# Laser_Array_Temp_Low_BRD_V2_2.net
KiCad netlist of a schematic drawn in EAGLE
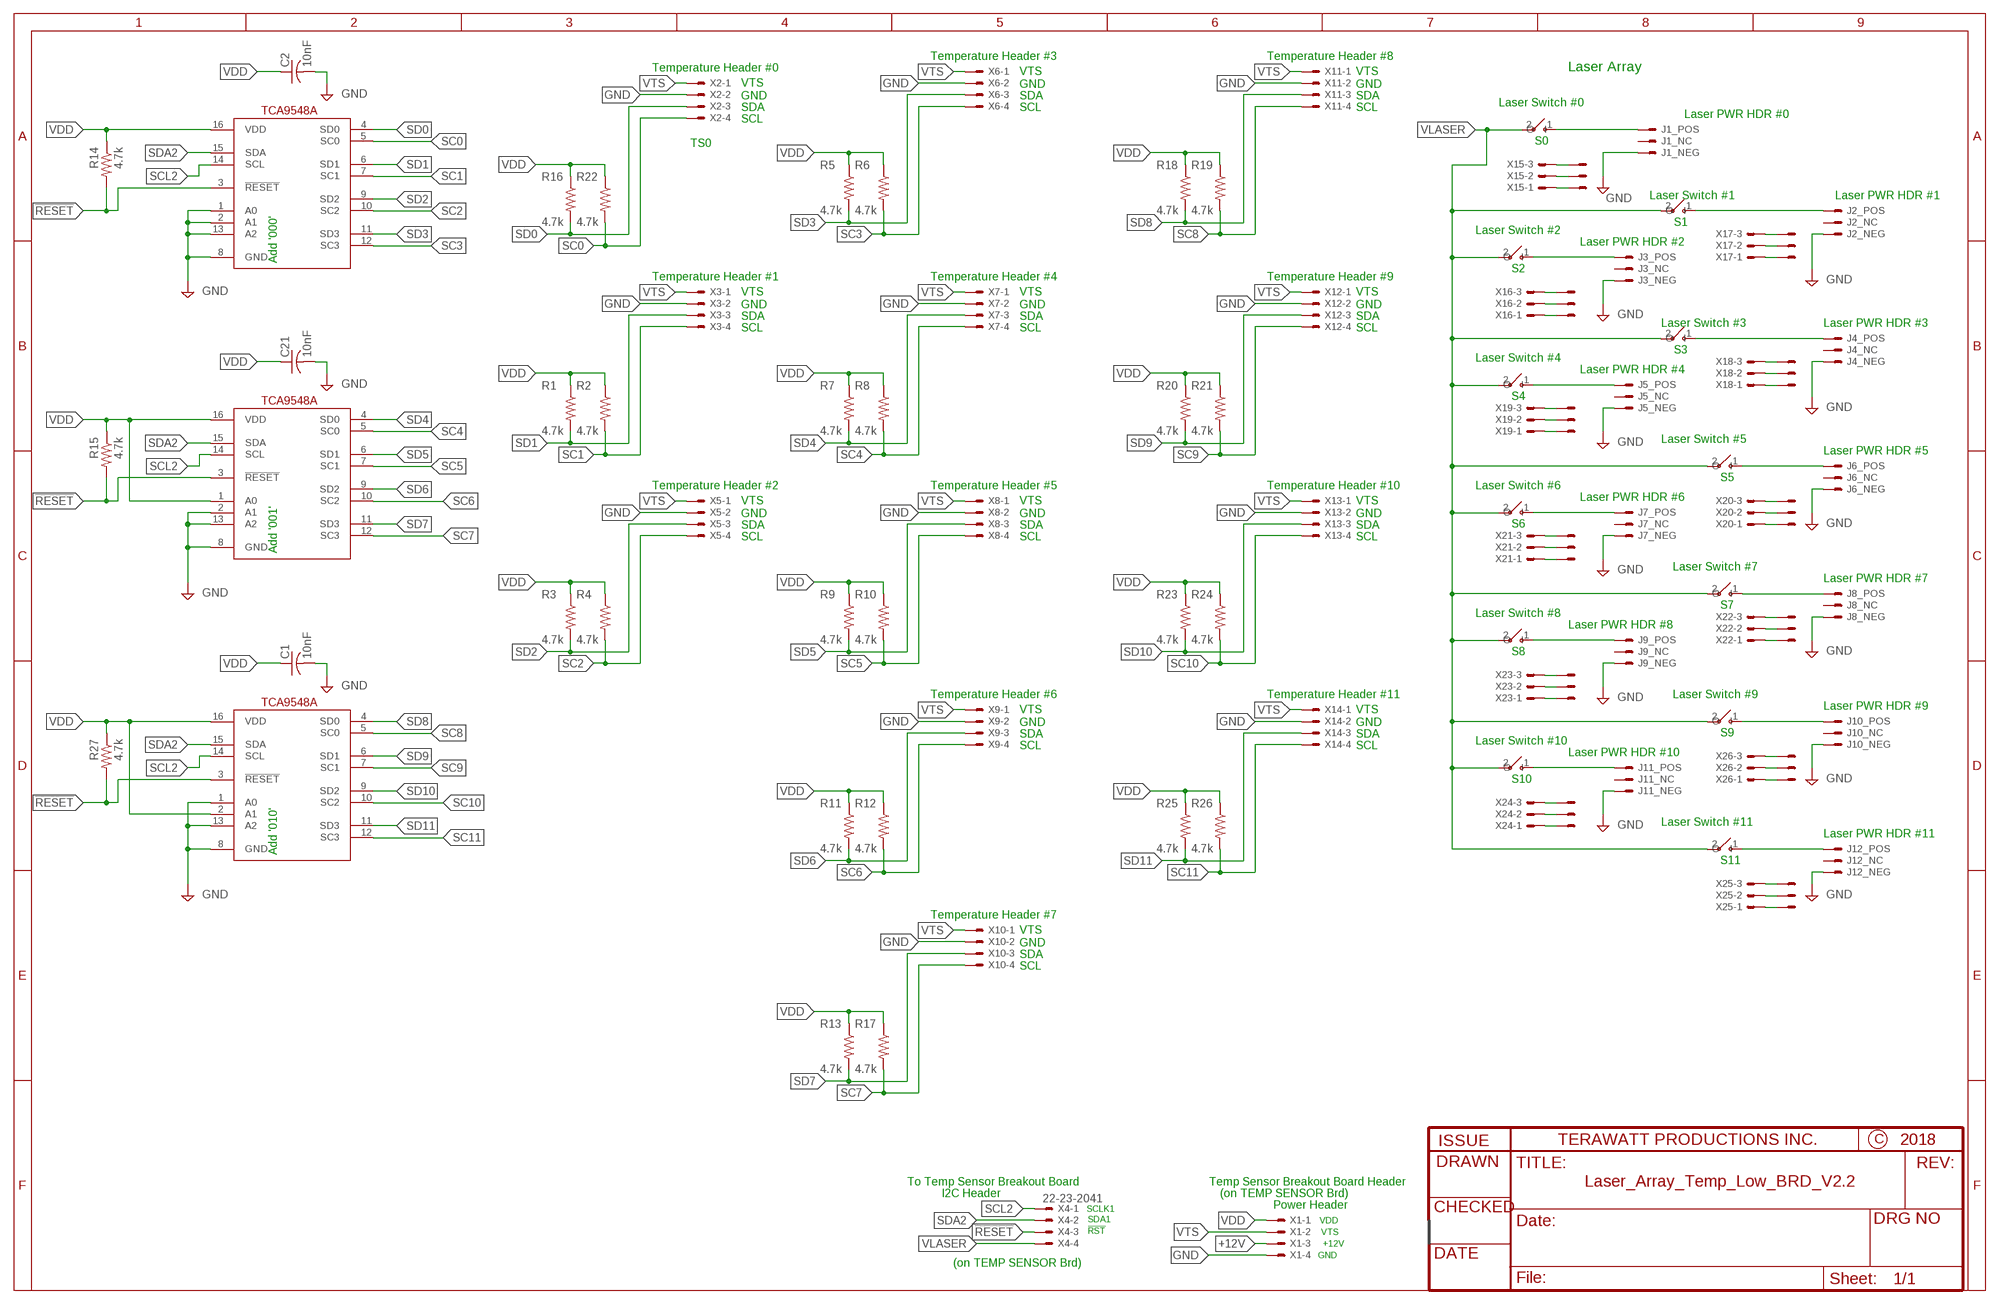
[diagram p0: schematic, sheet 1]

(export (version "E")
  (design (tool "Eeschema 10.0.6"))
  (components
    (comp (ref "C1")
      (value "10nF")
      (footprint "eagle-import:C0805")
      (libsource (lib "eagle-import") (part "C-USC0805"))
    )
    (comp (ref "C2")
      (value "10nF")
      (footprint "eagle-import:C0805")
      (libsource (lib "eagle-import") (part "C-USC0805"))
    )
    (comp (ref "C21")
      (value "10nF")
      (footprint "eagle-import:C0805")
      (libsource (lib "eagle-import") (part "C-USC0805"))
    )
    (comp (ref "J1")
      (value "LASER_MOD")
      (footprint "eagle-import:LASER_MOD")
      (libsource (lib "eagle-import") (part "LASER_MOD"))
    )
    (comp (ref "J2")
      (value "LASER_MOD")
      (footprint "eagle-import:LASER_MOD")
      (libsource (lib "eagle-import") (part "LASER_MOD"))
    )
    (comp (ref "J3")
      (value "LASER_MOD")
      (footprint "eagle-import:LASER_MOD")
      (libsource (lib "eagle-import") (part "LASER_MOD"))
    )
    (comp (ref "J4")
      (value "LASER_MOD")
      (footprint "eagle-import:LASER_MOD")
      (libsource (lib "eagle-import") (part "LASER_MOD"))
    )
    (comp (ref "J5")
      (value "LASER_MOD")
      (footprint "eagle-import:LASER_MOD")
      (libsource (lib "eagle-import") (part "LASER_MOD"))
    )
    (comp (ref "J6")
      (value "LASER_MOD")
      (footprint "eagle-import:LASER_MOD")
      (libsource (lib "eagle-import") (part "LASER_MOD"))
    )
    (comp (ref "J7")
      (value "LASER_MOD")
      (footprint "eagle-import:LASER_MOD")
      (libsource (lib "eagle-import") (part "LASER_MOD"))
    )
    (comp (ref "J8")
      (value "LASER_MOD")
      (footprint "eagle-import:LASER_MOD")
      (libsource (lib "eagle-import") (part "LASER_MOD"))
    )
    (comp (ref "J9")
      (value "LASER_MOD")
      (footprint "eagle-import:LASER_MOD")
      (libsource (lib "eagle-import") (part "LASER_MOD"))
    )
    (comp (ref "J10")
      (value "LASER_MOD")
      (footprint "eagle-import:LASER_MOD")
      (libsource (lib "eagle-import") (part "LASER_MOD"))
    )
    (comp (ref "J11")
      (value "LASER_MOD")
      (footprint "eagle-import:LASER_MOD")
      (libsource (lib "eagle-import") (part "LASER_MOD"))
    )
    (comp (ref "J12")
      (value "LASER_MOD")
      (footprint "eagle-import:LASER_MOD")
      (libsource (lib "eagle-import") (part "LASER_MOD"))
    )
    (comp (ref "R1")
      (value "4.7k")
      (footprint "eagle-import:M0805")
      (libsource (lib "eagle-import") (part "R-US_M0805"))
    )
    (comp (ref "R2")
      (value "4.7k")
      (footprint "eagle-import:M0805")
      (libsource (lib "eagle-import") (part "R-US_M0805"))
    )
    (comp (ref "R3")
      (value "4.7k")
      (footprint "eagle-import:M0805")
      (libsource (lib "eagle-import") (part "R-US_M0805"))
    )
    (comp (ref "R4")
      (value "4.7k")
      (footprint "eagle-import:M0805")
      (libsource (lib "eagle-import") (part "R-US_M0805"))
    )
    (comp (ref "R5")
      (value "4.7k")
      (footprint "eagle-import:M0805")
      (libsource (lib "eagle-import") (part "R-US_M0805"))
    )
    (comp (ref "R6")
      (value "4.7k")
      (footprint "eagle-import:M0805")
      (libsource (lib "eagle-import") (part "R-US_M0805"))
    )
    (comp (ref "R7")
      (value "4.7k")
      (footprint "eagle-import:M0805")
      (libsource (lib "eagle-import") (part "R-US_M0805"))
    )
    (comp (ref "R8")
      (value "4.7k")
      (footprint "eagle-import:M0805")
      (libsource (lib "eagle-import") (part "R-US_M0805"))
    )
    (comp (ref "R9")
      (value "4.7k")
      (footprint "eagle-import:M0805")
      (libsource (lib "eagle-import") (part "R-US_M0805"))
    )
    (comp (ref "R10")
      (value "4.7k")
      (footprint "eagle-import:M0805")
      (libsource (lib "eagle-import") (part "R-US_M0805"))
    )
    (comp (ref "R11")
      (value "4.7k")
      (footprint "eagle-import:M0805")
      (libsource (lib "eagle-import") (part "R-US_M0805"))
    )
    (comp (ref "R12")
      (value "4.7k")
      (footprint "eagle-import:M0805")
      (libsource (lib "eagle-import") (part "R-US_M0805"))
    )
    (comp (ref "R13")
      (value "4.7k")
      (footprint "eagle-import:M0805")
      (libsource (lib "eagle-import") (part "R-US_M0805"))
    )
    (comp (ref "R14")
      (value "4.7k")
      (footprint "eagle-import:M0805")
      (libsource (lib "eagle-import") (part "R-US_M0805"))
    )
    (comp (ref "R15")
      (value "4.7k")
      (footprint "eagle-import:M0805")
      (libsource (lib "eagle-import") (part "R-US_M0805"))
    )
    (comp (ref "R16")
      (value "4.7k")
      (footprint "eagle-import:M0805")
      (libsource (lib "eagle-import") (part "R-US_M0805"))
    )
    (comp (ref "R17")
      (value "4.7k")
      (footprint "eagle-import:M0805")
      (libsource (lib "eagle-import") (part "R-US_M0805"))
    )
    (comp (ref "R18")
      (value "4.7k")
      (footprint "eagle-import:M0805")
      (libsource (lib "eagle-import") (part "R-US_M0805"))
    )
    (comp (ref "R19")
      (value "4.7k")
      (footprint "eagle-import:M0805")
      (libsource (lib "eagle-import") (part "R-US_M0805"))
    )
    (comp (ref "R20")
      (value "4.7k")
      (footprint "eagle-import:M0805")
      (libsource (lib "eagle-import") (part "R-US_M0805"))
    )
    (comp (ref "R21")
      (value "4.7k")
      (footprint "eagle-import:M0805")
      (libsource (lib "eagle-import") (part "R-US_M0805"))
    )
    (comp (ref "R22")
      (value "4.7k")
      (footprint "eagle-import:M0805")
      (libsource (lib "eagle-import") (part "R-US_M0805"))
    )
    (comp (ref "R23")
      (value "4.7k")
      (footprint "eagle-import:M0805")
      (libsource (lib "eagle-import") (part "R-US_M0805"))
    )
    (comp (ref "R24")
      (value "4.7k")
      (footprint "eagle-import:M0805")
      (libsource (lib "eagle-import") (part "R-US_M0805"))
    )
    (comp (ref "R25")
      (value "4.7k")
      (footprint "eagle-import:M0805")
      (libsource (lib "eagle-import") (part "R-US_M0805"))
    )
    (comp (ref "R26")
      (value "4.7k")
      (footprint "eagle-import:M0805")
      (libsource (lib "eagle-import") (part "R-US_M0805"))
    )
    (comp (ref "R27")
      (value "4.7k")
      (footprint "eagle-import:M0805")
      (libsource (lib "eagle-import") (part "R-US_M0805"))
    )
    (comp (ref "S13")
      (value "TOGGLE_SPST")
      (footprint "eagle-import:22-23-2021")
      (libsource (lib "eagle-import") (part "TOGGLE_SPST"))
    )
    (comp (ref "S14")
      (value "TOGGLE_SPST")
      (footprint "eagle-import:22-23-2021")
      (libsource (lib "eagle-import") (part "TOGGLE_SPST"))
    )
    (comp (ref "S15")
      (value "TOGGLE_SPST")
      (footprint "eagle-import:22-23-2021")
      (libsource (lib "eagle-import") (part "TOGGLE_SPST"))
    )
    (comp (ref "S16")
      (value "TOGGLE_SPST")
      (footprint "eagle-import:22-23-2021")
      (libsource (lib "eagle-import") (part "TOGGLE_SPST"))
    )
    (comp (ref "S17")
      (value "TOGGLE_SPST")
      (footprint "eagle-import:22-23-2021")
      (libsource (lib "eagle-import") (part "TOGGLE_SPST"))
    )
    (comp (ref "S18")
      (value "TOGGLE_SPST")
      (footprint "eagle-import:22-23-2021")
      (libsource (lib "eagle-import") (part "TOGGLE_SPST"))
    )
    (comp (ref "S19")
      (value "TOGGLE_SPST")
      (footprint "eagle-import:22-23-2021")
      (libsource (lib "eagle-import") (part "TOGGLE_SPST"))
    )
    (comp (ref "S20")
      (value "TOGGLE_SPST")
      (footprint "eagle-import:22-23-2021")
      (libsource (lib "eagle-import") (part "TOGGLE_SPST"))
    )
    (comp (ref "S21")
      (value "TOGGLE_SPST")
      (footprint "eagle-import:22-23-2021")
      (libsource (lib "eagle-import") (part "TOGGLE_SPST"))
    )
    (comp (ref "S22")
      (value "TOGGLE_SPST")
      (footprint "eagle-import:22-23-2021")
      (libsource (lib "eagle-import") (part "TOGGLE_SPST"))
    )
    (comp (ref "S23")
      (value "TOGGLE_SPST")
      (footprint "eagle-import:22-23-2021")
      (libsource (lib "eagle-import") (part "TOGGLE_SPST"))
    )
    (comp (ref "S24")
      (value "TOGGLE_SPST")
      (footprint "eagle-import:22-23-2021")
      (libsource (lib "eagle-import") (part "TOGGLE_SPST"))
    )
    (comp (ref "U$1")
      (value "SINGLE_PAD")
      (footprint "eagle-import:SINGLE_PAD")
      (libsource (lib "eagle-import") (part "SINGLE_PAD"))
    )
    (comp (ref "U$2")
      (value "SINGLE_PAD")
      (footprint "eagle-import:SINGLE_PAD")
      (libsource (lib "eagle-import") (part "SINGLE_PAD"))
    )
    (comp (ref "U$3")
      (value "SINGLE_PAD")
      (footprint "eagle-import:SINGLE_PAD")
      (libsource (lib "eagle-import") (part "SINGLE_PAD"))
    )
    (comp (ref "U$4")
      (value "SINGLE_PAD")
      (footprint "eagle-import:SINGLE_PAD")
      (libsource (lib "eagle-import") (part "SINGLE_PAD"))
    )
    (comp (ref "U$5")
      (value "SINGLE_PAD")
      (footprint "eagle-import:SINGLE_PAD")
      (libsource (lib "eagle-import") (part "SINGLE_PAD"))
    )
    (comp (ref "U$6")
      (value "SINGLE_PAD")
      (footprint "eagle-import:SINGLE_PAD")
      (libsource (lib "eagle-import") (part "SINGLE_PAD"))
    )
    (comp (ref "U$7")
      (value "SINGLE_PAD")
      (footprint "eagle-import:SINGLE_PAD")
      (libsource (lib "eagle-import") (part "SINGLE_PAD"))
    )
    (comp (ref "U$8")
      (value "SINGLE_PAD")
      (footprint "eagle-import:SINGLE_PAD")
      (libsource (lib "eagle-import") (part "SINGLE_PAD"))
    )
    (comp (ref "U$9")
      (value "SINGLE_PAD")
      (footprint "eagle-import:SINGLE_PAD")
      (libsource (lib "eagle-import") (part "SINGLE_PAD"))
    )
    (comp (ref "U$10")
      (value "SINGLE_PAD")
      (footprint "eagle-import:SINGLE_PAD")
      (libsource (lib "eagle-import") (part "SINGLE_PAD"))
    )
    (comp (ref "U$11")
      (value "SINGLE_PAD")
      (footprint "eagle-import:SINGLE_PAD")
      (libsource (lib "eagle-import") (part "SINGLE_PAD"))
    )
    (comp (ref "U$12")
      (value "SINGLE_PAD")
      (footprint "eagle-import:SINGLE_PAD")
      (libsource (lib "eagle-import") (part "SINGLE_PAD"))
    )
    (comp (ref "U$13")
      (value "SINGLE_PAD")
      (footprint "eagle-import:SINGLE_PAD")
      (libsource (lib "eagle-import") (part "SINGLE_PAD"))
    )
    (comp (ref "U$14")
      (value "SINGLE_PAD")
      (footprint "eagle-import:SINGLE_PAD")
      (libsource (lib "eagle-import") (part "SINGLE_PAD"))
    )
    (comp (ref "U$15")
      (value "SINGLE_PAD")
      (footprint "eagle-import:SINGLE_PAD")
      (libsource (lib "eagle-import") (part "SINGLE_PAD"))
    )
    (comp (ref "U$16")
      (value "SINGLE_PAD")
      (footprint "eagle-import:SINGLE_PAD")
      (libsource (lib "eagle-import") (part "SINGLE_PAD"))
    )
    (comp (ref "U$17")
      (value "SINGLE_PAD")
      (footprint "eagle-import:SINGLE_PAD")
      (libsource (lib "eagle-import") (part "SINGLE_PAD"))
    )
    (comp (ref "U$18")
      (value "SINGLE_PAD")
      (footprint "eagle-import:SINGLE_PAD")
      (libsource (lib "eagle-import") (part "SINGLE_PAD"))
    )
    (comp (ref "U$19")
      (value "SINGLE_PAD")
      (footprint "eagle-import:SINGLE_PAD")
      (libsource (lib "eagle-import") (part "SINGLE_PAD"))
    )
    (comp (ref "U$20")
      (value "SINGLE_PAD")
      (footprint "eagle-import:SINGLE_PAD")
      (libsource (lib "eagle-import") (part "SINGLE_PAD"))
    )
    (comp (ref "U$21")
      (value "SINGLE_PAD")
      (footprint "eagle-import:SINGLE_PAD")
      (libsource (lib "eagle-import") (part "SINGLE_PAD"))
    )
    (comp (ref "U$22")
      (value "SINGLE_PAD")
      (footprint "eagle-import:SINGLE_PAD")
      (libsource (lib "eagle-import") (part "SINGLE_PAD"))
    )
    (comp (ref "U$23")
      (value "SINGLE_PAD")
      (footprint "eagle-import:SINGLE_PAD")
      (libsource (lib "eagle-import") (part "SINGLE_PAD"))
    )
    (comp (ref "U$24")
      (value "SINGLE_PAD")
      (footprint "eagle-import:SINGLE_PAD")
      (libsource (lib "eagle-import") (part "SINGLE_PAD"))
    )
    (comp (ref "U$25")
      (value "SINGLE_PAD")
      (footprint "eagle-import:SINGLE_PAD")
      (libsource (lib "eagle-import") (part "SINGLE_PAD"))
    )
    (comp (ref "U$26")
      (value "SINGLE_PAD")
      (footprint "eagle-import:SINGLE_PAD")
      (libsource (lib "eagle-import") (part "SINGLE_PAD"))
    )
    (comp (ref "U$27")
      (value "SINGLE_PAD")
      (footprint "eagle-import:SINGLE_PAD")
      (libsource (lib "eagle-import") (part "SINGLE_PAD"))
    )
    (comp (ref "U$28")
      (value "SINGLE_PAD")
      (footprint "eagle-import:SINGLE_PAD")
      (libsource (lib "eagle-import") (part "SINGLE_PAD"))
    )
    (comp (ref "U$29")
      (value "SINGLE_PAD")
      (footprint "eagle-import:SINGLE_PAD")
      (libsource (lib "eagle-import") (part "SINGLE_PAD"))
    )
    (comp (ref "U$30")
      (value "SINGLE_PAD")
      (footprint "eagle-import:SINGLE_PAD")
      (libsource (lib "eagle-import") (part "SINGLE_PAD"))
    )
    (comp (ref "U$31")
      (value "SINGLE_PAD")
      (footprint "eagle-import:SINGLE_PAD")
      (libsource (lib "eagle-import") (part "SINGLE_PAD"))
    )
    (comp (ref "U$32")
      (value "SINGLE_PAD")
      (footprint "eagle-import:SINGLE_PAD")
      (libsource (lib "eagle-import") (part "SINGLE_PAD"))
    )
    (comp (ref "U$33")
      (value "SINGLE_PAD")
      (footprint "eagle-import:SINGLE_PAD")
      (libsource (lib "eagle-import") (part "SINGLE_PAD"))
    )
    (comp (ref "U$34")
      (value "SINGLE_PAD")
      (footprint "eagle-import:SINGLE_PAD")
      (libsource (lib "eagle-import") (part "SINGLE_PAD"))
    )
    (comp (ref "U$35")
      (value "SINGLE_PAD")
      (footprint "eagle-import:SINGLE_PAD")
      (libsource (lib "eagle-import") (part "SINGLE_PAD"))
    )
    (comp (ref "U$36")
      (value "SINGLE_PAD")
      (footprint "eagle-import:SINGLE_PAD")
      (libsource (lib "eagle-import") (part "SINGLE_PAD"))
    )
    (comp (ref "U1")
      (value "TCA9546A")
      (footprint "eagle-import:SOIC16N")
      (libsource (lib "eagle-import") (part "TCA9546A"))
    )
    (comp (ref "U2")
      (value "TCA9546A")
      (footprint "eagle-import:SOIC16N")
      (libsource (lib "eagle-import") (part "TCA9546A"))
    )
    (comp (ref "U3")
      (value "TCA9546A")
      (footprint "eagle-import:SOIC16N")
      (libsource (lib "eagle-import") (part "TCA9546A"))
    )
    (comp (ref "X1")
      (value "22-23-2041")
      (footprint "eagle-import:22-23-2041")
      (fields (field (name "MF") "MOLEX"))
      (libsource (lib "eagle-import") (part "22-23-2041"))
    )
    (comp (ref "X2")
      (value "22-23-2041")
      (footprint "eagle-import:22-23-2041")
      (fields (field (name "MF") "MOLEX"))
      (libsource (lib "eagle-import") (part "22-23-2041"))
    )
    (comp (ref "X3")
      (value "22-23-2041")
      (footprint "eagle-import:22-23-2041")
      (fields (field (name "MF") "MOLEX"))
      (libsource (lib "eagle-import") (part "22-23-2041"))
    )
    (comp (ref "X4")
      (value "22-23-2041")
      (footprint "eagle-import:22-23-2041")
      (fields (field (name "MF") "MOLEX"))
      (libsource (lib "eagle-import") (part "22-23-2041"))
    )
    (comp (ref "X5")
      (value "22-23-2041")
      (footprint "eagle-import:22-23-2041")
      (fields (field (name "MF") "MOLEX"))
      (libsource (lib "eagle-import") (part "22-23-2041"))
    )
    (comp (ref "X6")
      (value "22-23-2041")
      (footprint "eagle-import:22-23-2041")
      (fields (field (name "MF") "MOLEX"))
      (libsource (lib "eagle-import") (part "22-23-2041"))
    )
    (comp (ref "X7")
      (value "22-23-2041")
      (footprint "eagle-import:22-23-2041")
      (fields (field (name "MF") "MOLEX"))
      (libsource (lib "eagle-import") (part "22-23-2041"))
    )
    (comp (ref "X8")
      (value "22-23-2041")
      (footprint "eagle-import:22-23-2041")
      (fields (field (name "MF") "MOLEX"))
      (libsource (lib "eagle-import") (part "22-23-2041"))
    )
    (comp (ref "X9")
      (value "22-23-2041")
      (footprint "eagle-import:22-23-2041")
      (fields (field (name "MF") "MOLEX"))
      (libsource (lib "eagle-import") (part "22-23-2041"))
    )
    (comp (ref "X10")
      (value "22-23-2041")
      (footprint "eagle-import:22-23-2041")
      (fields (field (name "MF") "MOLEX"))
      (libsource (lib "eagle-import") (part "22-23-2041"))
    )
    (comp (ref "X11")
      (value "22-23-2041")
      (footprint "eagle-import:22-23-2041")
      (fields (field (name "MF") "MOLEX"))
      (libsource (lib "eagle-import") (part "22-23-2041"))
    )
    (comp (ref "X12")
      (value "22-23-2041")
      (footprint "eagle-import:22-23-2041")
      (fields (field (name "MF") "MOLEX"))
      (libsource (lib "eagle-import") (part "22-23-2041"))
    )
    (comp (ref "X13")
      (value "22-23-2041")
      (footprint "eagle-import:22-23-2041")
      (fields (field (name "MF") "MOLEX"))
      (libsource (lib "eagle-import") (part "22-23-2041"))
    )
    (comp (ref "X14")
      (value "22-23-2041")
      (footprint "eagle-import:22-23-2041")
      (fields (field (name "MF") "MOLEX"))
      (libsource (lib "eagle-import") (part "22-23-2041"))
    )
    (comp (ref "X15")
      (value "22-23-2031")
      (footprint "eagle-import:22-23-2031")
      (fields (field (name "MF") "MOLEX"))
      (libsource (lib "eagle-import") (part "22-23-2031"))
    )
    (comp (ref "X16")
      (value "22-23-2031")
      (footprint "eagle-import:22-23-2031")
      (fields (field (name "MF") "MOLEX"))
      (libsource (lib "eagle-import") (part "22-23-2031"))
    )
    (comp (ref "X17")
      (value "22-23-2031")
      (footprint "eagle-import:22-23-2031")
      (fields (field (name "MF") "MOLEX"))
      (libsource (lib "eagle-import") (part "22-23-2031"))
    )
    (comp (ref "X18")
      (value "22-23-2031")
      (footprint "eagle-import:22-23-2031")
      (fields (field (name "MF") "MOLEX"))
      (libsource (lib "eagle-import") (part "22-23-2031"))
    )
    (comp (ref "X19")
      (value "22-23-2031")
      (footprint "eagle-import:22-23-2031")
      (fields (field (name "MF") "MOLEX"))
      (libsource (lib "eagle-import") (part "22-23-2031"))
    )
    (comp (ref "X20")
      (value "22-23-2031")
      (footprint "eagle-import:22-23-2031")
      (fields (field (name "MF") "MOLEX"))
      (libsource (lib "eagle-import") (part "22-23-2031"))
    )
    (comp (ref "X21")
      (value "22-23-2031")
      (footprint "eagle-import:22-23-2031")
      (fields (field (name "MF") "MOLEX"))
      (libsource (lib "eagle-import") (part "22-23-2031"))
    )
    (comp (ref "X22")
      (value "22-23-2031")
      (footprint "eagle-import:22-23-2031")
      (fields (field (name "MF") "MOLEX"))
      (libsource (lib "eagle-import") (part "22-23-2031"))
    )
    (comp (ref "X23")
      (value "22-23-2031")
      (footprint "eagle-import:22-23-2031")
      (fields (field (name "MF") "MOLEX"))
      (libsource (lib "eagle-import") (part "22-23-2031"))
    )
    (comp (ref "X24")
      (value "22-23-2031")
      (footprint "eagle-import:22-23-2031")
      (fields (field (name "MF") "MOLEX"))
      (libsource (lib "eagle-import") (part "22-23-2031"))
    )
    (comp (ref "X25")
      (value "22-23-2031")
      (footprint "eagle-import:22-23-2031")
      (fields (field (name "MF") "MOLEX"))
      (libsource (lib "eagle-import") (part "22-23-2031"))
    )
    (comp (ref "X26")
      (value "22-23-2031")
      (footprint "eagle-import:22-23-2031")
      (fields (field (name "MF") "MOLEX"))
      (libsource (lib "eagle-import") (part "22-23-2031"))
    )
  )
  (nets
    (net (code "1") (name "+12V") (class "Default")
      (node (ref "X1") (pin "3") (pinfunction "S_3") (pintype "passive"))
    )
    (net (code "2") (name "/~{RESET}") (class "Default")
      (node (ref "R14") (pin "2") (pinfunction "2_2") (pintype "passive"))
      (node (ref "R15") (pin "2") (pinfunction "2_2") (pintype "passive"))
      (node (ref "R27") (pin "2") (pinfunction "2_2") (pintype "passive"))
      (node (ref "U1") (pin "3") (pinfunction "~{RESET}_3") (pintype "bidirectional"))
      (node (ref "U2") (pin "3") (pinfunction "~{RESET}_3") (pintype "bidirectional"))
      (node (ref "U3") (pin "3") (pinfunction "~{RESET}_3") (pintype "bidirectional"))
      (node (ref "X4") (pin "3") (pinfunction "S_3") (pintype "passive"))
    )
    (net (code "3") (name "GND") (class "Default")
      (node (ref "C1") (pin "2") (pinfunction "2_2") (pintype "passive"))
      (node (ref "C2") (pin "2") (pinfunction "2_2") (pintype "passive"))
      (node (ref "C21") (pin "2") (pinfunction "2_2") (pintype "passive"))
      (node (ref "J1") (pin "3") (pinfunction "S_3") (pintype "passive"))
      (node (ref "J10") (pin "3") (pinfunction "S_3") (pintype "passive"))
      (node (ref "J11") (pin "3") (pinfunction "S_3") (pintype "passive"))
      (node (ref "J12") (pin "3") (pinfunction "S_3") (pintype "passive"))
      (node (ref "J2") (pin "3") (pinfunction "S_3") (pintype "passive"))
      (node (ref "J3") (pin "3") (pinfunction "S_3") (pintype "passive"))
      (node (ref "J4") (pin "3") (pinfunction "S_3") (pintype "passive"))
      (node (ref "J5") (pin "3") (pinfunction "S_3") (pintype "passive"))
      (node (ref "J6") (pin "3") (pinfunction "S_3") (pintype "passive"))
      (node (ref "J7") (pin "3") (pinfunction "S_3") (pintype "passive"))
      (node (ref "J8") (pin "3") (pinfunction "S_3") (pintype "passive"))
      (node (ref "J9") (pin "3") (pinfunction "S_3") (pintype "passive"))
      (node (ref "U1") (pin "1") (pinfunction "A0_1") (pintype "bidirectional"))
      (node (ref "U1") (pin "13") (pinfunction "A2_13") (pintype "bidirectional"))
      (node (ref "U1") (pin "2") (pinfunction "A1_2") (pintype "bidirectional"))
      (node (ref "U1") (pin "8") (pinfunction "GND_8") (pintype "bidirectional"))
      (node (ref "U2") (pin "13") (pinfunction "A2_13") (pintype "bidirectional"))
      (node (ref "U2") (pin "2") (pinfunction "A1_2") (pintype "bidirectional"))
      (node (ref "U2") (pin "8") (pinfunction "GND_8") (pintype "bidirectional"))
      (node (ref "U3") (pin "1") (pinfunction "A0_1") (pintype "bidirectional"))
      (node (ref "U3") (pin "13") (pinfunction "A2_13") (pintype "bidirectional"))
      (node (ref "U3") (pin "8") (pinfunction "GND_8") (pintype "bidirectional"))
      (node (ref "X1") (pin "4") (pinfunction "S_4") (pintype "passive"))
      (node (ref "X10") (pin "2") (pinfunction "S_2") (pintype "passive"))
      (node (ref "X11") (pin "2") (pinfunction "S_2") (pintype "passive"))
      (node (ref "X12") (pin "2") (pinfunction "S_2") (pintype "passive"))
      (node (ref "X13") (pin "2") (pinfunction "S_2") (pintype "passive"))
      (node (ref "X14") (pin "2") (pinfunction "S_2") (pintype "passive"))
      (node (ref "X2") (pin "2") (pinfunction "S_2") (pintype "passive"))
      (node (ref "X3") (pin "2") (pinfunction "S_2") (pintype "passive"))
      (node (ref "X5") (pin "2") (pinfunction "S_2") (pintype "passive"))
      (node (ref "X6") (pin "2") (pinfunction "S_2") (pintype "passive"))
      (node (ref "X7") (pin "2") (pinfunction "S_2") (pintype "passive"))
      (node (ref "X8") (pin "2") (pinfunction "S_2") (pintype "passive"))
      (node (ref "X9") (pin "2") (pinfunction "S_2") (pintype "passive"))
    )
    (net (code "4") (name "Net-(J1C-S)") (class "Default")
      (node (ref "J1") (pin "1") (pinfunction "S_1") (pintype "passive"))
      (node (ref "S16") (pin "1") (pinfunction "O_1") (pintype "bidirectional"))
    )
    (net (code "5") (name "Net-(J2C-S)") (class "Default")
      (node (ref "J2") (pin "1") (pinfunction "S_1") (pintype "passive"))
      (node (ref "S13") (pin "1") (pinfunction "O_1") (pintype "bidirectional"))
    )
    (net (code "6") (name "Net-(J3C-S)") (class "Default")
      (node (ref "J3") (pin "1") (pinfunction "S_1") (pintype "passive"))
      (node (ref "S14") (pin "1") (pinfunction "O_1") (pintype "bidirectional"))
    )
    (net (code "7") (name "Net-(J4C-S)") (class "Default")
      (node (ref "J4") (pin "1") (pinfunction "S_1") (pintype "passive"))
      (node (ref "S15") (pin "1") (pinfunction "O_1") (pintype "bidirectional"))
    )
    (net (code "8") (name "Net-(J5C-S)") (class "Default")
      (node (ref "J5") (pin "1") (pinfunction "S_1") (pintype "passive"))
      (node (ref "S17") (pin "1") (pinfunction "O_1") (pintype "bidirectional"))
    )
    (net (code "9") (name "Net-(J6C-S)") (class "Default")
      (node (ref "J6") (pin "1") (pinfunction "S_1") (pintype "passive"))
      (node (ref "S18") (pin "1") (pinfunction "O_1") (pintype "bidirectional"))
    )
    (net (code "10") (name "Net-(J7C-S)") (class "Default")
      (node (ref "J7") (pin "1") (pinfunction "S_1") (pintype "passive"))
      (node (ref "S19") (pin "1") (pinfunction "O_1") (pintype "bidirectional"))
    )
    (net (code "11") (name "Net-(J8C-S)") (class "Default")
      (node (ref "J8") (pin "1") (pinfunction "S_1") (pintype "passive"))
      (node (ref "S20") (pin "1") (pinfunction "O_1") (pintype "bidirectional"))
    )
    (net (code "12") (name "Net-(J9C-S)") (class "Default")
      (node (ref "J9") (pin "1") (pinfunction "S_1") (pintype "passive"))
      (node (ref "S21") (pin "1") (pinfunction "O_1") (pintype "bidirectional"))
    )
    (net (code "13") (name "Net-(J10C-S)") (class "Default")
      (node (ref "J10") (pin "1") (pinfunction "S_1") (pintype "passive"))
      (node (ref "S22") (pin "1") (pinfunction "O_1") (pintype "bidirectional"))
    )
    (net (code "14") (name "Net-(J11C-S)") (class "Default")
      (node (ref "J11") (pin "1") (pinfunction "S_1") (pintype "passive"))
      (node (ref "S23") (pin "1") (pinfunction "O_1") (pintype "bidirectional"))
    )
    (net (code "15") (name "Net-(J12C-S)") (class "Default")
      (node (ref "J12") (pin "1") (pinfunction "S_1") (pintype "passive"))
      (node (ref "S24") (pin "1") (pinfunction "O_1") (pintype "bidirectional"))
    )
    (net (code "16") (name "Net-(U$1-S)") (class "Default")
      (node (ref "U$1") (pin "1") (pinfunction "S_1") (pintype "passive"))
      (node (ref "X15") (pin "3") (pinfunction "S_3") (pintype "passive"))
    )
    (net (code "17") (name "Net-(U$2-S)") (class "Default")
      (node (ref "U$2") (pin "1") (pinfunction "S_1") (pintype "passive"))
      (node (ref "X15") (pin "2") (pinfunction "S_2") (pintype "passive"))
    )
    (net (code "18") (name "Net-(U$3-S)") (class "Default")
      (node (ref "U$3") (pin "1") (pinfunction "S_1") (pintype "passive"))
      (node (ref "X15") (pin "1") (pinfunction "S_1") (pintype "passive"))
    )
    (net (code "19") (name "Net-(U$4-S)") (class "Default")
      (node (ref "U$4") (pin "1") (pinfunction "S_1") (pintype "passive"))
      (node (ref "X16") (pin "3") (pinfunction "S_3") (pintype "passive"))
    )
    (net (code "20") (name "Net-(U$5-S)") (class "Default")
      (node (ref "U$5") (pin "1") (pinfunction "S_1") (pintype "passive"))
      (node (ref "X16") (pin "2") (pinfunction "S_2") (pintype "passive"))
    )
    (net (code "21") (name "Net-(U$6-S)") (class "Default")
      (node (ref "U$6") (pin "1") (pinfunction "S_1") (pintype "passive"))
      (node (ref "X16") (pin "1") (pinfunction "S_1") (pintype "passive"))
    )
    (net (code "22") (name "Net-(U$7-S)") (class "Default")
      (node (ref "U$7") (pin "1") (pinfunction "S_1") (pintype "passive"))
      (node (ref "X17") (pin "3") (pinfunction "S_3") (pintype "passive"))
    )
    (net (code "23") (name "Net-(U$8-S)") (class "Default")
      (node (ref "U$8") (pin "1") (pinfunction "S_1") (pintype "passive"))
      (node (ref "X17") (pin "2") (pinfunction "S_2") (pintype "passive"))
    )
    (net (code "24") (name "Net-(U$9-S)") (class "Default")
      (node (ref "U$9") (pin "1") (pinfunction "S_1") (pintype "passive"))
      (node (ref "X17") (pin "1") (pinfunction "S_1") (pintype "passive"))
    )
    (net (code "25") (name "Net-(U$10-S)") (class "Default")
      (node (ref "U$10") (pin "1") (pinfunction "S_1") (pintype "passive"))
      (node (ref "X18") (pin "3") (pinfunction "S_3") (pintype "passive"))
    )
    (net (code "26") (name "Net-(U$11-S)") (class "Default")
      (node (ref "U$11") (pin "1") (pinfunction "S_1") (pintype "passive"))
      (node (ref "X18") (pin "2") (pinfunction "S_2") (pintype "passive"))
    )
    (net (code "27") (name "Net-(U$12-S)") (class "Default")
      (node (ref "U$12") (pin "1") (pinfunction "S_1") (pintype "passive"))
      (node (ref "X18") (pin "1") (pinfunction "S_1") (pintype "passive"))
    )
    (net (code "28") (name "Net-(U$13-S)") (class "Default")
      (node (ref "U$13") (pin "1") (pinfunction "S_1") (pintype "passive"))
      (node (ref "X19") (pin "3") (pinfunction "S_3") (pintype "passive"))
    )
    (net (code "29") (name "Net-(U$14-S)") (class "Default")
      (node (ref "U$14") (pin "1") (pinfunction "S_1") (pintype "passive"))
      (node (ref "X19") (pin "2") (pinfunction "S_2") (pintype "passive"))
    )
    (net (code "30") (name "Net-(U$15-S)") (class "Default")
      (node (ref "U$15") (pin "1") (pinfunction "S_1") (pintype "passive"))
      (node (ref "X19") (pin "1") (pinfunction "S_1") (pintype "passive"))
    )
    (net (code "31") (name "Net-(U$16-S)") (class "Default")
      (node (ref "U$16") (pin "1") (pinfunction "S_1") (pintype "passive"))
      (node (ref "X20") (pin "3") (pinfunction "S_3") (pintype "passive"))
    )
    (net (code "32") (name "Net-(U$17-S)") (class "Default")
      (node (ref "U$17") (pin "1") (pinfunction "S_1") (pintype "passive"))
      (node (ref "X20") (pin "2") (pinfunction "S_2") (pintype "passive"))
    )
    (net (code "33") (name "Net-(U$18-S)") (class "Default")
      (node (ref "U$18") (pin "1") (pinfunction "S_1") (pintype "passive"))
      (node (ref "X20") (pin "1") (pinfunction "S_1") (pintype "passive"))
    )
    (net (code "34") (name "Net-(U$19-S)") (class "Default")
      (node (ref "U$19") (pin "1") (pinfunction "S_1") (pintype "passive"))
      (node (ref "X21") (pin "3") (pinfunction "S_3") (pintype "passive"))
    )
    (net (code "35") (name "Net-(U$20-S)") (class "Default")
      (node (ref "U$20") (pin "1") (pinfunction "S_1") (pintype "passive"))
      (node (ref "X21") (pin "2") (pinfunction "S_2") (pintype "passive"))
    )
    (net (code "36") (name "Net-(U$21-S)") (class "Default")
      (node (ref "U$21") (pin "1") (pinfunction "S_1") (pintype "passive"))
      (node (ref "X21") (pin "1") (pinfunction "S_1") (pintype "passive"))
    )
    (net (code "37") (name "Net-(U$22-S)") (class "Default")
      (node (ref "U$22") (pin "1") (pinfunction "S_1") (pintype "passive"))
      (node (ref "X22") (pin "3") (pinfunction "S_3") (pintype "passive"))
    )
    (net (code "38") (name "Net-(U$23-S)") (class "Default")
      (node (ref "U$23") (pin "1") (pinfunction "S_1") (pintype "passive"))
      (node (ref "X22") (pin "2") (pinfunction "S_2") (pintype "passive"))
    )
    (net (code "39") (name "Net-(U$24-S)") (class "Default")
      (node (ref "U$24") (pin "1") (pinfunction "S_1") (pintype "passive"))
      (node (ref "X22") (pin "1") (pinfunction "S_1") (pintype "passive"))
    )
    (net (code "40") (name "Net-(U$25-S)") (class "Default")
      (node (ref "U$25") (pin "1") (pinfunction "S_1") (pintype "passive"))
      (node (ref "X23") (pin "3") (pinfunction "S_3") (pintype "passive"))
    )
    (net (code "41") (name "Net-(U$26-S)") (class "Default")
      (node (ref "U$26") (pin "1") (pinfunction "S_1") (pintype "passive"))
      (node (ref "X23") (pin "2") (pinfunction "S_2") (pintype "passive"))
    )
    (net (code "42") (name "Net-(U$27-S)") (class "Default")
      (node (ref "U$27") (pin "1") (pinfunction "S_1") (pintype "passive"))
      (node (ref "X23") (pin "1") (pinfunction "S_1") (pintype "passive"))
    )
    (net (code "43") (name "Net-(U$28-S)") (class "Default")
      (node (ref "U$28") (pin "1") (pinfunction "S_1") (pintype "passive"))
      (node (ref "X24") (pin "3") (pinfunction "S_3") (pintype "passive"))
    )
    (net (code "44") (name "Net-(U$29-S)") (class "Default")
      (node (ref "U$29") (pin "1") (pinfunction "S_1") (pintype "passive"))
      (node (ref "X24") (pin "2") (pinfunction "S_2") (pintype "passive"))
    )
    (net (code "45") (name "Net-(U$30-S)") (class "Default")
      (node (ref "U$30") (pin "1") (pinfunction "S_1") (pintype "passive"))
      (node (ref "X24") (pin "1") (pinfunction "S_1") (pintype "passive"))
    )
    (net (code "46") (name "Net-(U$31-S)") (class "Default")
      (node (ref "U$31") (pin "1") (pinfunction "S_1") (pintype "passive"))
      (node (ref "X25") (pin "3") (pinfunction "S_3") (pintype "passive"))
    )
    (net (code "47") (name "Net-(U$32-S)") (class "Default")
      (node (ref "U$32") (pin "1") (pinfunction "S_1") (pintype "passive"))
      (node (ref "X25") (pin "2") (pinfunction "S_2") (pintype "passive"))
    )
    (net (code "48") (name "Net-(U$33-S)") (class "Default")
      (node (ref "U$33") (pin "1") (pinfunction "S_1") (pintype "passive"))
      (node (ref "X25") (pin "1") (pinfunction "S_1") (pintype "passive"))
    )
    (net (code "49") (name "Net-(U$34-S)") (class "Default")
      (node (ref "U$34") (pin "1") (pinfunction "S_1") (pintype "passive"))
      (node (ref "X26") (pin "3") (pinfunction "S_3") (pintype "passive"))
    )
    (net (code "50") (name "Net-(U$35-S)") (class "Default")
      (node (ref "U$35") (pin "1") (pinfunction "S_1") (pintype "passive"))
      (node (ref "X26") (pin "2") (pinfunction "S_2") (pintype "passive"))
    )
    (net (code "51") (name "Net-(U$36-S)") (class "Default")
      (node (ref "U$36") (pin "1") (pinfunction "S_1") (pintype "passive"))
      (node (ref "X26") (pin "1") (pinfunction "S_1") (pintype "passive"))
    )
    (net (code "52") (name "SC0") (class "Default")
      (node (ref "R22") (pin "2") (pinfunction "2_2") (pintype "passive"))
      (node (ref "U1") (pin "5") (pinfunction "SC0_5") (pintype "bidirectional"))
      (node (ref "X2") (pin "4") (pinfunction "S_4") (pintype "passive"))
    )
    (net (code "53") (name "SC1") (class "Default")
      (node (ref "R2") (pin "2") (pinfunction "2_2") (pintype "passive"))
      (node (ref "U1") (pin "7") (pinfunction "SC1_7") (pintype "bidirectional"))
      (node (ref "X3") (pin "4") (pinfunction "S_4") (pintype "passive"))
    )
    (net (code "54") (name "SC2") (class "Default")
      (node (ref "R4") (pin "2") (pinfunction "2_2") (pintype "passive"))
      (node (ref "U1") (pin "10") (pinfunction "SC2_10") (pintype "bidirectional"))
      (node (ref "X5") (pin "4") (pinfunction "S_4") (pintype "passive"))
    )
    (net (code "55") (name "SC3") (class "Default")
      (node (ref "R6") (pin "2") (pinfunction "2_2") (pintype "passive"))
      (node (ref "U1") (pin "12") (pinfunction "SC3_12") (pintype "bidirectional"))
      (node (ref "X6") (pin "4") (pinfunction "S_4") (pintype "passive"))
    )
    (net (code "56") (name "SC4") (class "Default")
      (node (ref "R8") (pin "2") (pinfunction "2_2") (pintype "passive"))
      (node (ref "U2") (pin "5") (pinfunction "SC0_5") (pintype "bidirectional"))
      (node (ref "X7") (pin "4") (pinfunction "S_4") (pintype "passive"))
    )
    (net (code "57") (name "SC5") (class "Default")
      (node (ref "R10") (pin "2") (pinfunction "2_2") (pintype "passive"))
      (node (ref "U2") (pin "7") (pinfunction "SC1_7") (pintype "bidirectional"))
      (node (ref "X8") (pin "4") (pinfunction "S_4") (pintype "passive"))
    )
    (net (code "58") (name "SC6") (class "Default")
      (node (ref "R12") (pin "2") (pinfunction "2_2") (pintype "passive"))
      (node (ref "U2") (pin "10") (pinfunction "SC2_10") (pintype "bidirectional"))
      (node (ref "X9") (pin "4") (pinfunction "S_4") (pintype "passive"))
    )
    (net (code "59") (name "SC7") (class "Default")
      (node (ref "R17") (pin "2") (pinfunction "2_2") (pintype "passive"))
      (node (ref "U2") (pin "12") (pinfunction "SC3_12") (pintype "bidirectional"))
      (node (ref "X10") (pin "4") (pinfunction "S_4") (pintype "passive"))
    )
    (net (code "60") (name "SC8") (class "Default")
      (node (ref "R19") (pin "2") (pinfunction "2_2") (pintype "passive"))
      (node (ref "U3") (pin "5") (pinfunction "SC0_5") (pintype "bidirectional"))
      (node (ref "X11") (pin "4") (pinfunction "S_4") (pintype "passive"))
    )
    (net (code "61") (name "SC9") (class "Default")
      (node (ref "R21") (pin "2") (pinfunction "2_2") (pintype "passive"))
      (node (ref "U3") (pin "7") (pinfunction "SC1_7") (pintype "bidirectional"))
      (node (ref "X12") (pin "4") (pinfunction "S_4") (pintype "passive"))
    )
    (net (code "62") (name "SC10") (class "Default")
      (node (ref "R24") (pin "2") (pinfunction "2_2") (pintype "passive"))
      (node (ref "U3") (pin "10") (pinfunction "SC2_10") (pintype "bidirectional"))
      (node (ref "X13") (pin "4") (pinfunction "S_4") (pintype "passive"))
    )
    (net (code "63") (name "SC11") (class "Default")
      (node (ref "R26") (pin "2") (pinfunction "2_2") (pintype "passive"))
      (node (ref "U3") (pin "12") (pinfunction "SC3_12") (pintype "bidirectional"))
      (node (ref "X14") (pin "4") (pinfunction "S_4") (pintype "passive"))
    )
    (net (code "64") (name "SCL2") (class "Default")
      (node (ref "U1") (pin "14") (pinfunction "SCL_14") (pintype "bidirectional"))
      (node (ref "U2") (pin "14") (pinfunction "SCL_14") (pintype "bidirectional"))
      (node (ref "U3") (pin "14") (pinfunction "SCL_14") (pintype "bidirectional"))
      (node (ref "X4") (pin "1") (pinfunction "S_1") (pintype "passive"))
    )
    (net (code "65") (name "SD0") (class "Default")
      (node (ref "R16") (pin "2") (pinfunction "2_2") (pintype "passive"))
      (node (ref "U1") (pin "4") (pinfunction "SD0_4") (pintype "bidirectional"))
      (node (ref "X2") (pin "3") (pinfunction "S_3") (pintype "passive"))
    )
    (net (code "66") (name "SD1") (class "Default")
      (node (ref "R1") (pin "2") (pinfunction "2_2") (pintype "passive"))
      (node (ref "U1") (pin "6") (pinfunction "SD1_6") (pintype "bidirectional"))
      (node (ref "X3") (pin "3") (pinfunction "S_3") (pintype "passive"))
    )
    (net (code "67") (name "SD2") (class "Default")
      (node (ref "R3") (pin "2") (pinfunction "2_2") (pintype "passive"))
      (node (ref "U1") (pin "9") (pinfunction "SD2_9") (pintype "bidirectional"))
      (node (ref "X5") (pin "3") (pinfunction "S_3") (pintype "passive"))
    )
    (net (code "68") (name "SD3") (class "Default")
      (node (ref "R5") (pin "2") (pinfunction "2_2") (pintype "passive"))
      (node (ref "U1") (pin "11") (pinfunction "SD3_11") (pintype "bidirectional"))
      (node (ref "X6") (pin "3") (pinfunction "S_3") (pintype "passive"))
    )
    (net (code "69") (name "SD4") (class "Default")
      (node (ref "R7") (pin "2") (pinfunction "2_2") (pintype "passive"))
      (node (ref "U2") (pin "4") (pinfunction "SD0_4") (pintype "bidirectional"))
      (node (ref "X7") (pin "3") (pinfunction "S_3") (pintype "passive"))
    )
    (net (code "70") (name "SD5") (class "Default")
      (node (ref "R9") (pin "2") (pinfunction "2_2") (pintype "passive"))
      (node (ref "U2") (pin "6") (pinfunction "SD1_6") (pintype "bidirectional"))
      (node (ref "X8") (pin "3") (pinfunction "S_3") (pintype "passive"))
    )
    (net (code "71") (name "SD6") (class "Default")
      (node (ref "R11") (pin "2") (pinfunction "2_2") (pintype "passive"))
      (node (ref "U2") (pin "9") (pinfunction "SD2_9") (pintype "bidirectional"))
      (node (ref "X9") (pin "3") (pinfunction "S_3") (pintype "passive"))
    )
    (net (code "72") (name "SD7") (class "Default")
      (node (ref "R13") (pin "2") (pinfunction "2_2") (pintype "passive"))
      (node (ref "U2") (pin "11") (pinfunction "SD3_11") (pintype "bidirectional"))
      (node (ref "X10") (pin "3") (pinfunction "S_3") (pintype "passive"))
    )
    (net (code "73") (name "SD8") (class "Default")
      (node (ref "R18") (pin "2") (pinfunction "2_2") (pintype "passive"))
      (node (ref "U3") (pin "4") (pinfunction "SD0_4") (pintype "bidirectional"))
      (node (ref "X11") (pin "3") (pinfunction "S_3") (pintype "passive"))
    )
    (net (code "74") (name "SD9") (class "Default")
      (node (ref "R20") (pin "2") (pinfunction "2_2") (pintype "passive"))
      (node (ref "U3") (pin "6") (pinfunction "SD1_6") (pintype "bidirectional"))
      (node (ref "X12") (pin "3") (pinfunction "S_3") (pintype "passive"))
    )
    (net (code "75") (name "SD10") (class "Default")
      (node (ref "R23") (pin "2") (pinfunction "2_2") (pintype "passive"))
      (node (ref "U3") (pin "9") (pinfunction "SD2_9") (pintype "bidirectional"))
      (node (ref "X13") (pin "3") (pinfunction "S_3") (pintype "passive"))
    )
    (net (code "76") (name "SD11") (class "Default")
      (node (ref "R25") (pin "2") (pinfunction "2_2") (pintype "passive"))
      (node (ref "U3") (pin "11") (pinfunction "SD3_11") (pintype "bidirectional"))
      (node (ref "X14") (pin "3") (pinfunction "S_3") (pintype "passive"))
    )
    (net (code "77") (name "SDA2") (class "Default")
      (node (ref "U1") (pin "15") (pinfunction "SDA_15") (pintype "bidirectional"))
      (node (ref "U2") (pin "15") (pinfunction "SDA_15") (pintype "bidirectional"))
      (node (ref "U3") (pin "15") (pinfunction "SDA_15") (pintype "bidirectional"))
      (node (ref "X4") (pin "2") (pinfunction "S_2") (pintype "passive"))
    )
    (net (code "78") (name "VDD") (class "Default")
      (node (ref "C1") (pin "1") (pinfunction "1_1") (pintype "passive"))
      (node (ref "C2") (pin "1") (pinfunction "1_1") (pintype "passive"))
      (node (ref "C21") (pin "1") (pinfunction "1_1") (pintype "passive"))
      (node (ref "R1") (pin "1") (pinfunction "1_1") (pintype "passive"))
      (node (ref "R10") (pin "1") (pinfunction "1_1") (pintype "passive"))
      (node (ref "R11") (pin "1") (pinfunction "1_1") (pintype "passive"))
      (node (ref "R12") (pin "1") (pinfunction "1_1") (pintype "passive"))
      (node (ref "R13") (pin "1") (pinfunction "1_1") (pintype "passive"))
      (node (ref "R14") (pin "1") (pinfunction "1_1") (pintype "passive"))
      (node (ref "R15") (pin "1") (pinfunction "1_1") (pintype "passive"))
      (node (ref "R16") (pin "1") (pinfunction "1_1") (pintype "passive"))
      (node (ref "R17") (pin "1") (pinfunction "1_1") (pintype "passive"))
      (node (ref "R18") (pin "1") (pinfunction "1_1") (pintype "passive"))
      (node (ref "R19") (pin "1") (pinfunction "1_1") (pintype "passive"))
      (node (ref "R2") (pin "1") (pinfunction "1_1") (pintype "passive"))
      (node (ref "R20") (pin "1") (pinfunction "1_1") (pintype "passive"))
      (node (ref "R21") (pin "1") (pinfunction "1_1") (pintype "passive"))
      (node (ref "R22") (pin "1") (pinfunction "1_1") (pintype "passive"))
      (node (ref "R23") (pin "1") (pinfunction "1_1") (pintype "passive"))
      (node (ref "R24") (pin "1") (pinfunction "1_1") (pintype "passive"))
      (node (ref "R25") (pin "1") (pinfunction "1_1") (pintype "passive"))
      (node (ref "R26") (pin "1") (pinfunction "1_1") (pintype "passive"))
      (node (ref "R27") (pin "1") (pinfunction "1_1") (pintype "passive"))
      (node (ref "R3") (pin "1") (pinfunction "1_1") (pintype "passive"))
      (node (ref "R4") (pin "1") (pinfunction "1_1") (pintype "passive"))
      (node (ref "R5") (pin "1") (pinfunction "1_1") (pintype "passive"))
      (node (ref "R6") (pin "1") (pinfunction "1_1") (pintype "passive"))
      (node (ref "R7") (pin "1") (pinfunction "1_1") (pintype "passive"))
      (node (ref "R8") (pin "1") (pinfunction "1_1") (pintype "passive"))
      (node (ref "R9") (pin "1") (pinfunction "1_1") (pintype "passive"))
      (node (ref "U1") (pin "16") (pinfunction "VDD_16") (pintype "bidirectional"))
      (node (ref "U2") (pin "1") (pinfunction "A0_1") (pintype "bidirectional"))
      (node (ref "U2") (pin "16") (pinfunction "VDD_16") (pintype "bidirectional"))
      (node (ref "U3") (pin "16") (pinfunction "VDD_16") (pintype "bidirectional"))
      (node (ref "U3") (pin "2") (pinfunction "A1_2") (pintype "bidirectional"))
      (node (ref "X1") (pin "1") (pinfunction "S_1") (pintype "passive"))
    )
    (net (code "79") (name "VLASER") (class "Default")
      (node (ref "S13") (pin "2") (pinfunction "I_2") (pintype "bidirectional"))
      (node (ref "S14") (pin "2") (pinfunction "I_2") (pintype "bidirectional"))
      (node (ref "S15") (pin "2") (pinfunction "I_2") (pintype "bidirectional"))
      (node (ref "S16") (pin "2") (pinfunction "I_2") (pintype "bidirectional"))
      (node (ref "S17") (pin "2") (pinfunction "I_2") (pintype "bidirectional"))
      (node (ref "S18") (pin "2") (pinfunction "I_2") (pintype "bidirectional"))
      (node (ref "S19") (pin "2") (pinfunction "I_2") (pintype "bidirectional"))
      (node (ref "S20") (pin "2") (pinfunction "I_2") (pintype "bidirectional"))
      (node (ref "S21") (pin "2") (pinfunction "I_2") (pintype "bidirectional"))
      (node (ref "S22") (pin "2") (pinfunction "I_2") (pintype "bidirectional"))
      (node (ref "S23") (pin "2") (pinfunction "I_2") (pintype "bidirectional"))
      (node (ref "S24") (pin "2") (pinfunction "I_2") (pintype "bidirectional"))
      (node (ref "X4") (pin "4") (pinfunction "S_4") (pintype "passive"))
    )
    (net (code "80") (name "VTS") (class "Default")
      (node (ref "X1") (pin "2") (pinfunction "S_2") (pintype "passive"))
      (node (ref "X10") (pin "1") (pinfunction "S_1") (pintype "passive"))
      (node (ref "X11") (pin "1") (pinfunction "S_1") (pintype "passive"))
      (node (ref "X12") (pin "1") (pinfunction "S_1") (pintype "passive"))
      (node (ref "X13") (pin "1") (pinfunction "S_1") (pintype "passive"))
      (node (ref "X14") (pin "1") (pinfunction "S_1") (pintype "passive"))
      (node (ref "X2") (pin "1") (pinfunction "S_1") (pintype "passive"))
      (node (ref "X3") (pin "1") (pinfunction "S_1") (pintype "passive"))
      (node (ref "X5") (pin "1") (pinfunction "S_1") (pintype "passive"))
      (node (ref "X6") (pin "1") (pinfunction "S_1") (pintype "passive"))
      (node (ref "X7") (pin "1") (pinfunction "S_1") (pintype "passive"))
      (node (ref "X8") (pin "1") (pinfunction "S_1") (pintype "passive"))
      (node (ref "X9") (pin "1") (pinfunction "S_1") (pintype "passive"))
    )
    (net (code "81") (name "unconnected-(J1A-S-Pad2)") (class "Default")
      (node (ref "J1") (pin "2") (pinfunction "S_2") (pintype "passive"))
    )
    (net (code "82") (name "unconnected-(J2A-S-Pad2)") (class "Default")
      (node (ref "J2") (pin "2") (pinfunction "S_2") (pintype "passive"))
    )
    (net (code "83") (name "unconnected-(J3A-S-Pad2)") (class "Default")
      (node (ref "J3") (pin "2") (pinfunction "S_2") (pintype "passive"))
    )
    (net (code "84") (name "unconnected-(J4A-S-Pad2)") (class "Default")
      (node (ref "J4") (pin "2") (pinfunction "S_2") (pintype "passive"))
    )
    (net (code "85") (name "unconnected-(J5A-S-Pad2)") (class "Default")
      (node (ref "J5") (pin "2") (pinfunction "S_2") (pintype "passive"))
    )
    (net (code "86") (name "unconnected-(J6A-S-Pad2)") (class "Default")
      (node (ref "J6") (pin "2") (pinfunction "S_2") (pintype "passive"))
    )
    (net (code "87") (name "unconnected-(J7A-S-Pad2)") (class "Default")
      (node (ref "J7") (pin "2") (pinfunction "S_2") (pintype "passive"))
    )
    (net (code "88") (name "unconnected-(J8A-S-Pad2)") (class "Default")
      (node (ref "J8") (pin "2") (pinfunction "S_2") (pintype "passive"))
    )
    (net (code "89") (name "unconnected-(J9A-S-Pad2)") (class "Default")
      (node (ref "J9") (pin "2") (pinfunction "S_2") (pintype "passive"))
    )
    (net (code "90") (name "unconnected-(J10A-S-Pad2)") (class "Default")
      (node (ref "J10") (pin "2") (pinfunction "S_2") (pintype "passive"))
    )
    (net (code "91") (name "unconnected-(J11A-S-Pad2)") (class "Default")
      (node (ref "J11") (pin "2") (pinfunction "S_2") (pintype "passive"))
    )
    (net (code "92") (name "unconnected-(J12A-S-Pad2)") (class "Default")
      (node (ref "J12") (pin "2") (pinfunction "S_2") (pintype "passive"))
    )
  )
)
